# GPRS-Tracker.net
KiCad netlist of a schematic drawn in EAGLE
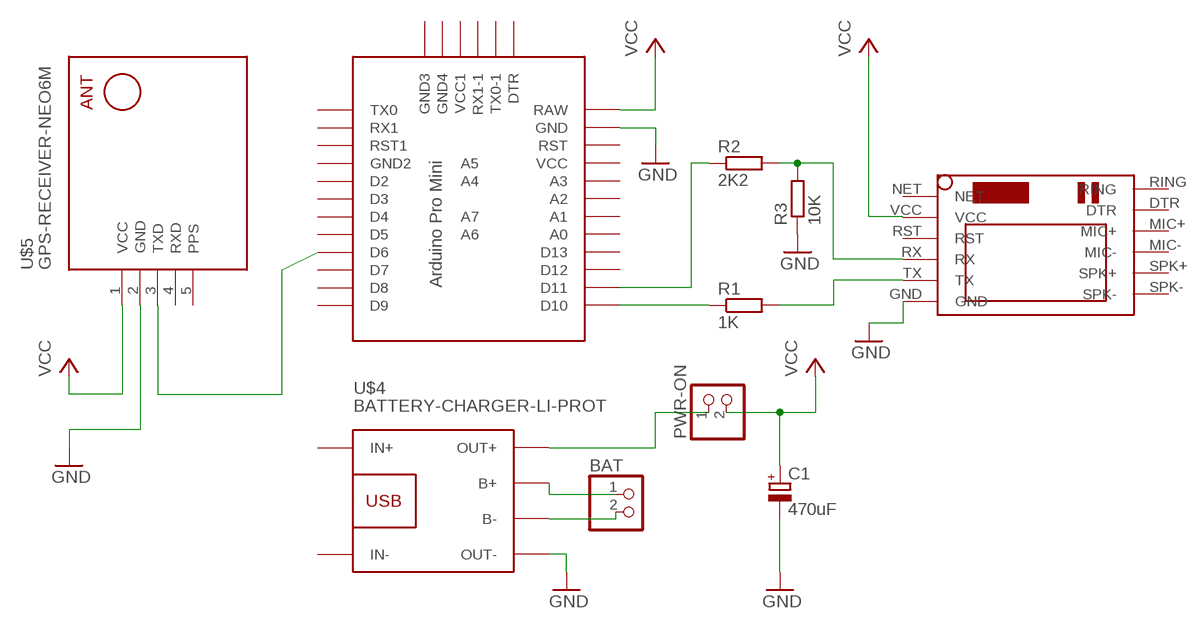
[diagram p0: schematic, sheet 1]

(export (version "E")
  (design (tool "Eeschema 10.0.6"))
  (components
    (comp (ref "BAT")
      (value "PINHD-1X2")
      (footprint "eagle-import:1X02")
      (libsource (lib "eagle-import") (part "PINHD-1X2"))
    )
    (comp (ref "C1")
      (value "470uF")
      (footprint "eagle-import:E3,5-8")
      (libsource (lib "eagle-import") (part "CPOL-EUE3.5-8"))
    )
    (comp (ref "PWR-ON")
      (value "PINHD-1X2")
      (footprint "eagle-import:1X02")
      (libsource (lib "eagle-import") (part "PINHD-1X2"))
    )
    (comp (ref "R1")
      (value "1K")
      (footprint "eagle-import:0204_7")
      (libsource (lib "eagle-import") (part "R-EU_0204/7"))
    )
    (comp (ref "R2")
      (value "2K2")
      (footprint "eagle-import:0204_7")
      (libsource (lib "eagle-import") (part "R-EU_0204/7"))
    )
    (comp (ref "R3")
      (value "10K")
      (footprint "eagle-import:0204_7")
      (libsource (lib "eagle-import") (part "R-EU_0204/7"))
    )
    (comp (ref "U$1")
      (value "PRO-MINI-2")
      (footprint "eagle-import:PRO-MINI-2")
      (libsource (lib "eagle-import") (part "PRO-MINI-2"))
    )
    (comp (ref "U$2")
      (value "SIM800LMODULE")
      (footprint "eagle-import:SIM800LMODULE")
      (libsource (lib "eagle-import") (part "SIM800LMODULE"))
    )
    (comp (ref "U$4")
      (value "BATTERY-CHARGER-LI-PROT")
      (footprint "eagle-import:BATTERY-CHARGER-LI-PROT")
      (libsource (lib "eagle-import") (part "BATTERY-CHARGER-LI-PROT"))
    )
    (comp (ref "U$5")
      (value "GPS-RECEIVER-NEO6M")
      (footprint "eagle-import:GPS-RECEIVER-NEO6M")
      (libsource (lib "eagle-import") (part "GPS-RECEIVER-NEO6M"))
    )
  )
  (nets
    (net (code "1") (name "/PPS") (class "Default")
      (node (ref "U$5") (pin "5") (pinfunction "PPS_5") (pintype "power_in"))
    )
    (net (code "2") (name "/RXD") (class "Default")
      (node (ref "U$5") (pin "4") (pinfunction "RXD_4") (pintype "power_in"))
    )
    (net (code "3") (name "GND") (class "Default")
      (node (ref "C1") (pin "-") (pinfunction "-_-") (pintype "passive"))
      (node (ref "R3") (pin "1") (pinfunction "1_1") (pintype "passive"))
      (node (ref "U$1") (pin "GND") (pinfunction "GND_GND") (pintype "bidirectional"))
      (node (ref "U$2") (pin "GND") (pinfunction "GND_GND") (pintype "bidirectional"))
      (node (ref "U$4") (pin "OUT-") (pinfunction "OUT-_OUT-") (pintype "bidirectional"))
      (node (ref "U$5") (pin "2") (pinfunction "GND_2") (pintype "bidirectional"))
    )
    (net (code "4") (name "Net-(BAT-Pad1)") (class "Default")
      (node (ref "BAT") (pin "1") (pinfunction "1_1") (pintype "passive"))
      (node (ref "U$4") (pin "B+") (pinfunction "B+_B+") (pintype "bidirectional"))
    )
    (net (code "5") (name "Net-(BAT-Pad2)") (class "Default")
      (node (ref "BAT") (pin "2") (pinfunction "2_2") (pintype "passive"))
      (node (ref "U$4") (pin "B-") (pinfunction "B-_B-") (pintype "bidirectional"))
    )
    (net (code "6") (name "Net-(PWR-ON-Pad1)") (class "Default")
      (node (ref "PWR-ON") (pin "1") (pinfunction "1_1") (pintype "passive"))
      (node (ref "U$4") (pin "OUT+") (pinfunction "OUT+_OUT+") (pintype "bidirectional"))
    )
    (net (code "7") (name "Net-(R1-Pad1)") (class "Default")
      (node (ref "R1") (pin "1") (pinfunction "1_1") (pintype "passive"))
      (node (ref "U$1") (pin "D10") (pinfunction "D10_D10") (pintype "bidirectional"))
    )
    (net (code "8") (name "Net-(R1-Pad2)") (class "Default")
      (node (ref "R1") (pin "2") (pinfunction "2_2") (pintype "passive"))
      (node (ref "U$2") (pin "TX") (pinfunction "TX_TX") (pintype "bidirectional"))
    )
    (net (code "9") (name "Net-(R2-Pad1)") (class "Default")
      (node (ref "R2") (pin "1") (pinfunction "1_1") (pintype "passive"))
      (node (ref "U$1") (pin "D11") (pinfunction "D11_D11") (pintype "bidirectional"))
    )
    (net (code "10") (name "Net-(R2-Pad2)") (class "Default")
      (node (ref "R2") (pin "2") (pinfunction "2_2") (pintype "passive"))
      (node (ref "R3") (pin "2") (pinfunction "2_2") (pintype "passive"))
      (node (ref "U$2") (pin "RX") (pinfunction "RX_RX") (pintype "bidirectional"))
    )
    (net (code "11") (name "Net-(U$5-TXD)") (class "Default")
      (node (ref "U$1") (pin "D6") (pinfunction "D6_D6") (pintype "bidirectional"))
      (node (ref "U$5") (pin "3") (pinfunction "TXD_3") (pintype "bidirectional"))
    )
    (net (code "12") (name "VCC") (class "Default")
      (node (ref "C1") (pin "+") (pinfunction "+_+") (pintype "passive"))
      (node (ref "PWR-ON") (pin "2") (pinfunction "2_2") (pintype "passive"))
      (node (ref "U$1") (pin "RAW") (pinfunction "RAW_RAW") (pintype "bidirectional"))
      (node (ref "U$2") (pin "VCC") (pinfunction "VCC_VCC") (pintype "bidirectional"))
      (node (ref "U$5") (pin "1") (pinfunction "VCC_1") (pintype "bidirectional"))
    )
    (net (code "13") (name "unconnected-(U$1-GND2-PadGND1)") (class "Default")
      (node (ref "U$1") (pin "GND1") (pinfunction "GND2_GND1") (pintype "bidirectional"))
    )
    (net (code "14") (name "unconnected-(U$1-GND3-PadGND2)") (class "Default")
      (node (ref "U$1") (pin "GND2") (pinfunction "GND3_GND2") (pintype "bidirectional"))
    )
    (net (code "15") (name "unconnected-(U$1-GND4-PadGND3)") (class "Default")
      (node (ref "U$1") (pin "GND3") (pinfunction "GND4_GND3") (pintype "bidirectional"))
    )
    (net (code "16") (name "unconnected-(U$1-PadA0)") (class "Default")
      (node (ref "U$1") (pin "A0") (pinfunction "A0_A0") (pintype "bidirectional"))
    )
    (net (code "17") (name "unconnected-(U$1-PadA1)") (class "Default")
      (node (ref "U$1") (pin "A1") (pinfunction "A1_A1") (pintype "bidirectional"))
    )
    (net (code "18") (name "unconnected-(U$1-PadA2)") (class "Default")
      (node (ref "U$1") (pin "A2") (pinfunction "A2_A2") (pintype "bidirectional"))
    )
    (net (code "19") (name "unconnected-(U$1-PadA3)") (class "Default")
      (node (ref "U$1") (pin "A3") (pinfunction "A3_A3") (pintype "bidirectional"))
    )
    (net (code "20") (name "unconnected-(U$1-PadA4)") (class "Default")
      (node (ref "U$1") (pin "A4") (pinfunction "A4_A4") (pintype "bidirectional"))
    )
    (net (code "21") (name "unconnected-(U$1-PadA5)") (class "Default")
      (node (ref "U$1") (pin "A5") (pinfunction "A5_A5") (pintype "bidirectional"))
    )
    (net (code "22") (name "unconnected-(U$1-PadA6)") (class "Default")
      (node (ref "U$1") (pin "A6") (pinfunction "A6_A6") (pintype "bidirectional"))
    )
    (net (code "23") (name "unconnected-(U$1-PadA7)") (class "Default")
      (node (ref "U$1") (pin "A7") (pinfunction "A7_A7") (pintype "bidirectional"))
    )
    (net (code "24") (name "unconnected-(U$1-PadD2)") (class "Default")
      (node (ref "U$1") (pin "D2") (pinfunction "D2_D2") (pintype "bidirectional"))
    )
    (net (code "25") (name "unconnected-(U$1-PadD3)") (class "Default")
      (node (ref "U$1") (pin "D3") (pinfunction "D3_D3") (pintype "bidirectional"))
    )
    (net (code "26") (name "unconnected-(U$1-PadD4)") (class "Default")
      (node (ref "U$1") (pin "D4") (pinfunction "D4_D4") (pintype "bidirectional"))
    )
    (net (code "27") (name "unconnected-(U$1-PadD5)") (class "Default")
      (node (ref "U$1") (pin "D5") (pinfunction "D5_D5") (pintype "bidirectional"))
    )
    (net (code "28") (name "unconnected-(U$1-PadD7)") (class "Default")
      (node (ref "U$1") (pin "D7") (pinfunction "D7_D7") (pintype "bidirectional"))
    )
    (net (code "29") (name "unconnected-(U$1-PadD8)") (class "Default")
      (node (ref "U$1") (pin "D8") (pinfunction "D8_D8") (pintype "bidirectional"))
    )
    (net (code "30") (name "unconnected-(U$1-PadD9)") (class "Default")
      (node (ref "U$1") (pin "D9") (pinfunction "D9_D9") (pintype "bidirectional"))
    )
    (net (code "31") (name "unconnected-(U$1-PadD12)") (class "Default")
      (node (ref "U$1") (pin "D12") (pinfunction "D12_D12") (pintype "bidirectional"))
    )
    (net (code "32") (name "unconnected-(U$1-PadD13)") (class "Default")
      (node (ref "U$1") (pin "D13") (pinfunction "D13_D13") (pintype "bidirectional"))
    )
    (net (code "33") (name "unconnected-(U$1-PadDTR)") (class "Default")
      (node (ref "U$1") (pin "DTR") (pinfunction "DTR_DTR") (pintype "bidirectional"))
    )
    (net (code "34") (name "unconnected-(U$1-PadRST)") (class "Default")
      (node (ref "U$1") (pin "RST") (pinfunction "RST_RST") (pintype "bidirectional"))
    )
    (net (code "35") (name "unconnected-(U$1-PadRST1)") (class "Default")
      (node (ref "U$1") (pin "RST1") (pinfunction "RST1_RST1") (pintype "bidirectional"))
    )
    (net (code "36") (name "unconnected-(U$1-PadRX1)") (class "Default")
      (node (ref "U$1") (pin "RX1") (pinfunction "RX1_RX1") (pintype "bidirectional"))
    )
    (net (code "37") (name "unconnected-(U$1-PadRX1-1)") (class "Default")
      (node (ref "U$1") (pin "RX1-1") (pinfunction "RX1-1_RX1-1") (pintype "bidirectional"))
    )
    (net (code "38") (name "unconnected-(U$1-PadTX0)") (class "Default")
      (node (ref "U$1") (pin "TX0") (pinfunction "TX0_TX0") (pintype "bidirectional"))
    )
    (net (code "39") (name "unconnected-(U$1-PadTX0-1)") (class "Default")
      (node (ref "U$1") (pin "TX0-1") (pinfunction "TX0-1_TX0-1") (pintype "bidirectional"))
    )
    (net (code "40") (name "unconnected-(U$1-PadVCC)") (class "Default")
      (node (ref "U$1") (pin "VCC") (pinfunction "VCC_VCC") (pintype "bidirectional"))
    )
    (net (code "41") (name "unconnected-(U$1-PadVCC1)") (class "Default")
      (node (ref "U$1") (pin "VCC1") (pinfunction "VCC1_VCC1") (pintype "bidirectional"))
    )
    (net (code "42") (name "unconnected-(U$2-PadDTR)") (class "Default")
      (node (ref "U$2") (pin "DTR") (pinfunction "DTR_DTR") (pintype "bidirectional"))
    )
    (net (code "43") (name "unconnected-(U$2-PadMIC+)") (class "Default")
      (node (ref "U$2") (pin "MIC+") (pinfunction "MIC+_MIC+") (pintype "bidirectional"))
    )
    (net (code "44") (name "unconnected-(U$2-PadMIC-)") (class "Default")
      (node (ref "U$2") (pin "MIC-") (pinfunction "MIC-_MIC-") (pintype "bidirectional"))
    )
    (net (code "45") (name "unconnected-(U$2-PadNET)") (class "Default")
      (node (ref "U$2") (pin "NET") (pinfunction "NET_NET") (pintype "bidirectional"))
    )
    (net (code "46") (name "unconnected-(U$2-PadRING)") (class "Default")
      (node (ref "U$2") (pin "RING") (pinfunction "RING_RING") (pintype "bidirectional"))
    )
    (net (code "47") (name "unconnected-(U$2-PadRST)") (class "Default")
      (node (ref "U$2") (pin "RST") (pinfunction "RST_RST") (pintype "bidirectional"))
    )
    (net (code "48") (name "unconnected-(U$2-PadSPK+)") (class "Default")
      (node (ref "U$2") (pin "SPK+") (pinfunction "SPK+_SPK+") (pintype "bidirectional"))
    )
    (net (code "49") (name "unconnected-(U$2-PadSPK-)") (class "Default")
      (node (ref "U$2") (pin "SPK-") (pinfunction "SPK-_SPK-") (pintype "bidirectional"))
    )
    (net (code "50") (name "unconnected-(U$4-PadIN+)") (class "Default")
      (node (ref "U$4") (pin "IN+") (pinfunction "IN+_IN+") (pintype "bidirectional"))
    )
    (net (code "51") (name "unconnected-(U$4-PadIN-)") (class "Default")
      (node (ref "U$4") (pin "IN-") (pinfunction "IN-_IN-") (pintype "bidirectional"))
    )
  )
)
